# IMU_final.net
KiCad netlist of a schematic drawn in EAGLE
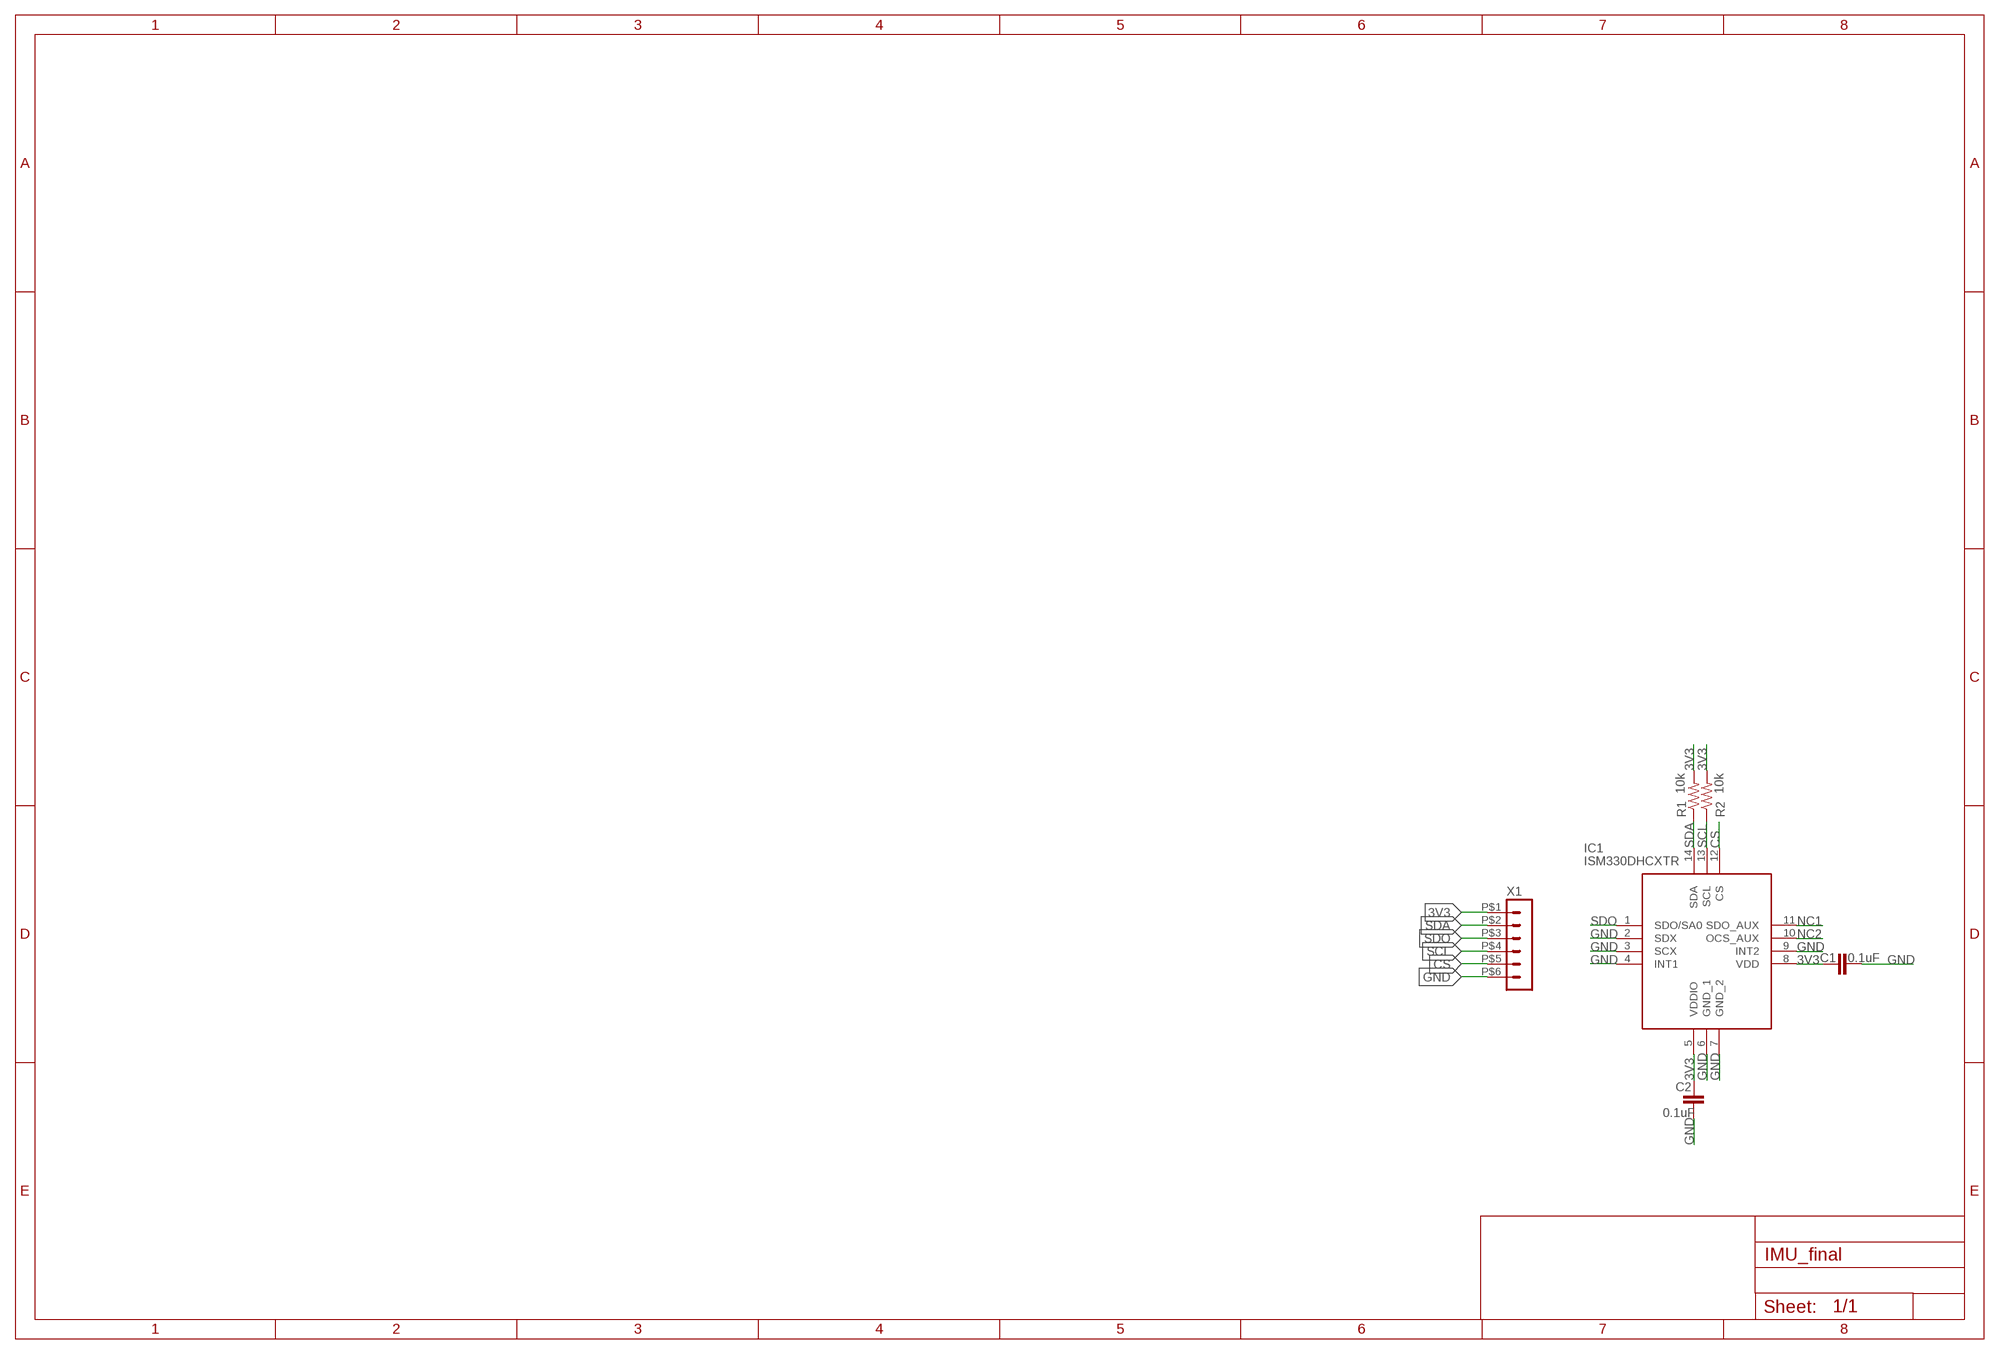
[diagram p0: schematic, sheet 1]

(export (version "E")
  (design (tool "Eeschema 10.0.6"))
  (components
    (comp (ref "C1")
      (value "0.1uF")
      (footprint "eagle-import:0603")
      (libsource (lib "eagle-import") (part "0.1UF-0603-25V-(+80/-20%)"))
    )
    (comp (ref "C2")
      (value "0.1uF")
      (footprint "eagle-import:0603")
      (libsource (lib "eagle-import") (part "0.1UF-0603-25V-(+80/-20%)"))
    )
    (comp (ref "IC1")
      (value "ISM330DHCXTR")
      (footprint "eagle-import:LGA-14(2.5X3X0.86)")
      (fields (field (name "MOUSER_PART_NUMBER") "511-ISM330DHCXTR"))
      (libsource (lib "eagle-import") (part "ISM330DHCXTR"))
    )
    (comp (ref "R1")
      (value "10k")
      (footprint "eagle-import:0603")
      (libsource (lib "eagle-import") (part "10KOHM-0603-1/10W-1%"))
    )
    (comp (ref "R2")
      (value "10k")
      (footprint "eagle-import:0603")
      (libsource (lib "eagle-import") (part "10KOHM-0603-1/10W-1%"))
    )
    (comp (ref "X1")
      (value "HEADER_POS6_43045-0600")
      (footprint "eagle-import:43045-0600")
      (libsource (lib "eagle-import") (part "HEADER_POS6_?43045-0600"))
    )
  )
  (nets
    (net (code "1") (name "/NC1") (class "Default")
      (node (ref "IC1") (pin "11") (pinfunction "SDO_AUX_11") (pintype "bidirectional"))
    )
    (net (code "2") (name "/NC2") (class "Default")
      (node (ref "IC1") (pin "10") (pinfunction "OCS_AUX_10") (pintype "bidirectional"))
    )
    (net (code "3") (name "3V3") (class "Default")
      (node (ref "C1") (pin "1") (pinfunction "1_1") (pintype "passive"))
      (node (ref "C2") (pin "1") (pinfunction "1_1") (pintype "passive"))
      (node (ref "IC1") (pin "5") (pinfunction "VDDIO_5") (pintype "bidirectional"))
      (node (ref "IC1") (pin "8") (pinfunction "VDD_8") (pintype "bidirectional"))
      (node (ref "R1") (pin "2") (pinfunction "2_2") (pintype "passive"))
      (node (ref "R2") (pin "2") (pinfunction "2_2") (pintype "passive"))
      (node (ref "X1") (pin "P$1") (pinfunction "1_P$1") (pintype "passive"))
    )
    (net (code "4") (name "CS") (class "Default")
      (node (ref "IC1") (pin "12") (pinfunction "CS_12") (pintype "bidirectional"))
      (node (ref "X1") (pin "P$5") (pinfunction "5_P$5") (pintype "passive"))
    )
    (net (code "5") (name "GND") (class "Default")
      (node (ref "C1") (pin "2") (pinfunction "2_2") (pintype "passive"))
      (node (ref "C2") (pin "2") (pinfunction "2_2") (pintype "passive"))
      (node (ref "IC1") (pin "2") (pinfunction "SDX_2") (pintype "bidirectional"))
      (node (ref "IC1") (pin "3") (pinfunction "SCX_3") (pintype "bidirectional"))
      (node (ref "IC1") (pin "4") (pinfunction "INT1_4") (pintype "bidirectional"))
      (node (ref "IC1") (pin "6") (pinfunction "GND_1_6") (pintype "bidirectional"))
      (node (ref "IC1") (pin "7") (pinfunction "GND_2_7") (pintype "bidirectional"))
      (node (ref "IC1") (pin "9") (pinfunction "INT2_9") (pintype "bidirectional"))
      (node (ref "X1") (pin "P$6") (pinfunction "6_P$6") (pintype "passive"))
    )
    (net (code "6") (name "SCL") (class "Default")
      (node (ref "IC1") (pin "13") (pinfunction "SCL_13") (pintype "bidirectional"))
      (node (ref "R2") (pin "1") (pinfunction "1_1") (pintype "passive"))
      (node (ref "X1") (pin "P$4") (pinfunction "4_P$4") (pintype "passive"))
    )
    (net (code "7") (name "SDA") (class "Default")
      (node (ref "IC1") (pin "14") (pinfunction "SDA_14") (pintype "bidirectional"))
      (node (ref "R1") (pin "1") (pinfunction "1_1") (pintype "passive"))
      (node (ref "X1") (pin "P$2") (pinfunction "2_P$2") (pintype "passive"))
    )
    (net (code "8") (name "SDO") (class "Default")
      (node (ref "IC1") (pin "1") (pinfunction "SDO/SA0_1") (pintype "bidirectional"))
      (node (ref "X1") (pin "P$3") (pinfunction "3_P$3") (pintype "passive"))
    )
  )
)
